# MCP16252_v1.net
KiCad netlist of a schematic drawn in EAGLE
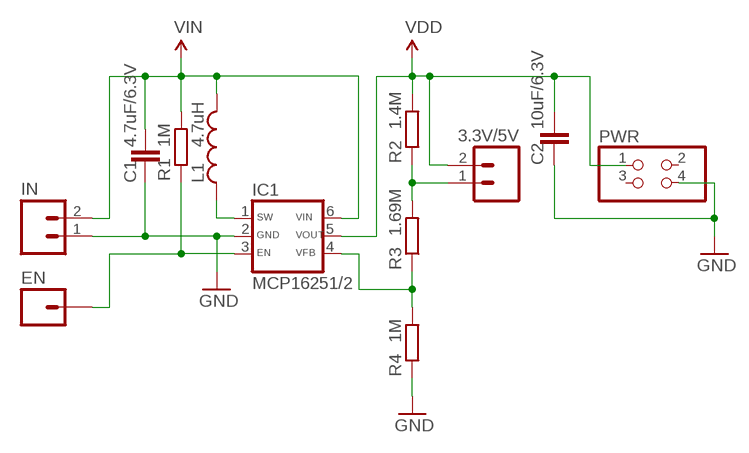
[diagram p0: schematic, sheet 1]

(export (version "E")
  (design (tool "Eeschema 10.0.6"))
  (components
    (comp (ref "3.3V/5V")
      (value "M02PTH")
      (footprint "eagle-import:1X02")
      (libsource (lib "eagle-import") (part "M02PTH"))
    )
    (comp (ref "C1")
      (value "4.7uF/6.3V")
      (footprint "eagle-import:C805")
      (libsource (lib "eagle-import") (part "CAPACITOR_NPOL-0805"))
    )
    (comp (ref "C2")
      (value "10uF/6.3V")
      (footprint "eagle-import:C805")
      (libsource (lib "eagle-import") (part "CAPACITOR_NPOL-0805"))
    )
    (comp (ref "EN")
      (value "M01PTH")
      (footprint "eagle-import:1X01")
      (libsource (lib "eagle-import") (part "M01PTH"))
    )
    (comp (ref "IC1")
      (value "MCP16251/2")
      (footprint "eagle-import:SOT-23-6")
      (libsource (lib "eagle-import") (part "MCP16251/2"))
    )
    (comp (ref "IN")
      (value "M02PTH")
      (footprint "eagle-import:1X02")
      (libsource (lib "eagle-import") (part "M02PTH"))
    )
    (comp (ref "L1")
      (value "4.7uH")
      (footprint "eagle-import:1007")
      (libsource (lib "eagle-import") (part "INDUCTOR1007"))
    )
    (comp (ref "PWR")
      (value "PINHD-2X2")
      (footprint "eagle-import:2X02")
      (libsource (lib "eagle-import") (part "PINHD-2X2"))
    )
    (comp (ref "R1")
      (value "1M")
      (footprint "eagle-import:R603")
      (libsource (lib "eagle-import") (part "RESISTOR-0603"))
    )
    (comp (ref "R2")
      (value "1.4M")
      (footprint "eagle-import:R603")
      (libsource (lib "eagle-import") (part "RESISTOR-0603"))
    )
    (comp (ref "R3")
      (value "1.69M")
      (footprint "eagle-import:R603")
      (libsource (lib "eagle-import") (part "RESISTOR-0603"))
    )
    (comp (ref "R4")
      (value "1M")
      (footprint "eagle-import:R603")
      (libsource (lib "eagle-import") (part "RESISTOR-0603"))
    )
  )
  (nets
    (net (code "1") (name "GND") (class "Default")
      (node (ref "C1") (pin "2") (pinfunction "2_2") (pintype "passive"))
      (node (ref "C2") (pin "2") (pinfunction "2_2") (pintype "passive"))
      (node (ref "IC1") (pin "2") (pinfunction "GND_2") (pintype "passive"))
      (node (ref "IN") (pin "1") (pinfunction "1_1") (pintype "passive"))
      (node (ref "PWR") (pin "4") (pinfunction "4_4") (pintype "passive"))
      (node (ref "R4") (pin "1") (pinfunction "1_1") (pintype "passive"))
    )
    (net (code "2") (name "Net-(3.3V/5V-Pad1)") (class "Default")
      (node (ref "3.3V/5V") (pin "1") (pinfunction "1_1") (pintype "passive"))
      (node (ref "R2") (pin "1") (pinfunction "1_1") (pintype "passive"))
      (node (ref "R3") (pin "2") (pinfunction "2_2") (pintype "passive"))
    )
    (net (code "3") (name "Net-(IC1-EN)") (class "Default")
      (node (ref "EN") (pin "1") (pinfunction "1_1") (pintype "passive"))
      (node (ref "IC1") (pin "3") (pinfunction "EN_3") (pintype "passive"))
      (node (ref "R1") (pin "1") (pinfunction "1_1") (pintype "passive"))
    )
    (net (code "4") (name "Net-(IC1-SW)") (class "Default")
      (node (ref "IC1") (pin "1") (pinfunction "SW_1") (pintype "passive"))
      (node (ref "L1") (pin "1") (pinfunction "1_1") (pintype "passive"))
    )
    (net (code "5") (name "Net-(IC1-VFB)") (class "Default")
      (node (ref "IC1") (pin "4") (pinfunction "VFB_4") (pintype "passive"))
      (node (ref "R3") (pin "1") (pinfunction "1_1") (pintype "passive"))
      (node (ref "R4") (pin "2") (pinfunction "2_2") (pintype "passive"))
    )
    (net (code "6") (name "VDD") (class "Default")
      (node (ref "3.3V/5V") (pin "2") (pinfunction "2_2") (pintype "passive"))
      (node (ref "C2") (pin "1") (pinfunction "1_1") (pintype "passive"))
      (node (ref "IC1") (pin "5") (pinfunction "VOUT_5") (pintype "passive"))
      (node (ref "PWR") (pin "1") (pinfunction "1_1") (pintype "passive"))
      (node (ref "R2") (pin "2") (pinfunction "2_2") (pintype "passive"))
    )
    (net (code "7") (name "VIN") (class "Default")
      (node (ref "C1") (pin "1") (pinfunction "1_1") (pintype "passive"))
      (node (ref "IC1") (pin "6") (pinfunction "VIN_6") (pintype "passive"))
      (node (ref "IN") (pin "2") (pinfunction "2_2") (pintype "passive"))
      (node (ref "L1") (pin "2") (pinfunction "2_2") (pintype "passive"))
      (node (ref "R1") (pin "2") (pinfunction "2_2") (pintype "passive"))
    )
    (net (code "8") (name "unconnected-(PWR-Pad2)") (class "Default")
      (node (ref "PWR") (pin "2") (pinfunction "2_2") (pintype "passive"))
    )
    (net (code "9") (name "unconnected-(PWR-Pad3)") (class "Default")
      (node (ref "PWR") (pin "3") (pinfunction "3_3") (pintype "passive"))
    )
  )
)
